# SCT12A0_BOOST.net
KiCad netlist of a schematic drawn in Altium Designer
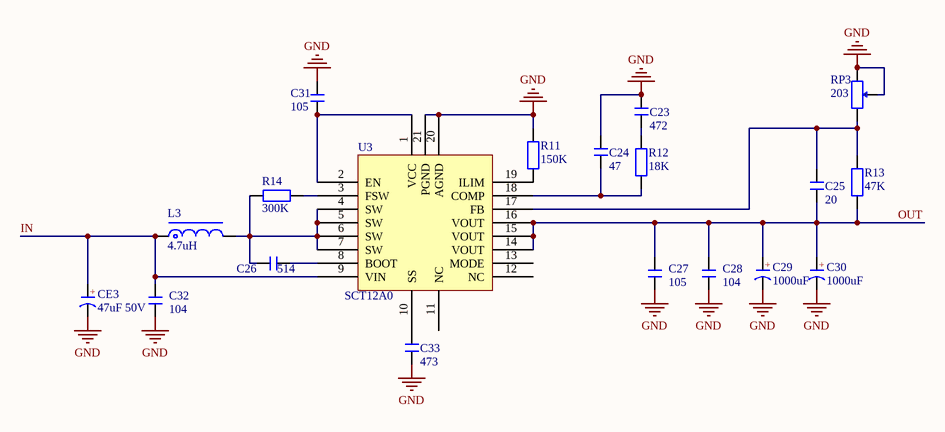
[diagram p0: SCT12A0 BOOST.SchDoc]

(export (version "E")
  (design (tool "Eeschema 10.0.6"))
  (components
    (comp (ref "C23")
      (value "472")
      (footprint "C 0805_L")
      (description "贴片电容")
      (libsource (lib "01 - 电容-电阻-电感") (part "C"))
    )
    (comp (ref "C24")
      (value "47")
      (footprint "C 0805_L")
      (description "贴片电容")
      (libsource (lib "01 - 电容-电阻-电感") (part "C"))
    )
    (comp (ref "C25")
      (value "20")
      (footprint "C 0805_L")
      (description "贴片电容")
      (libsource (lib "01 - 电容-电阻-电感") (part "C"))
    )
    (comp (ref "C26")
      (value "514")
      (footprint "C 0805_L")
      (description "贴片电容")
      (libsource (lib "01 - 电容-电阻-电感") (part "C"))
    )
    (comp (ref "C27")
      (value "105")
      (footprint "C 0805_L")
      (description "贴片电容")
      (libsource (lib "01 - 电容-电阻-电感") (part "C"))
    )
    (comp (ref "C28")
      (value "104")
      (footprint "C 0805_L")
      (description "贴片电容")
      (libsource (lib "01 - 电容-电阻-电感") (part "C"))
    )
    (comp (ref "C29")
      (value "1000uF")
      (footprint "CAP 7.5*16*25")
      (description "直插电解电容")
      (libsource (lib "01 - 电容-电阻-电感") (part "CE"))
    )
    (comp (ref "C30")
      (value "1000uF")
      (footprint "CAP 5.0*12.5*20")
      (description "直插电解电容")
      (libsource (lib "01 - 电容-电阻-电感") (part "CE"))
    )
    (comp (ref "C31")
      (value "105")
      (footprint "C 0805_L")
      (description "贴片电容")
      (libsource (lib "01 - 电容-电阻-电感") (part "C"))
    )
    (comp (ref "C32")
      (value "104")
      (footprint "C 0805_L")
      (description "贴片电容")
      (libsource (lib "01 - 电容-电阻-电感") (part "C"))
    )
    (comp (ref "C33")
      (value "473")
      (footprint "C 0805_L")
      (description "贴片电容")
      (libsource (lib "01 - 电容-电阻-电感") (part "C"))
    )
    (comp (ref "CE3")
      (value "47uF 50V")
      (footprint "CM C(5*5.4)")
      (description "贴片电解电容")
      (libsource (lib "01 - 电容-电阻-电感") (part "CE_SMD"))
    )
    (comp (ref "L3")
      (value "4.7uH")
      (footprint "CDRH127")
      (description "功率屏蔽电感")
      (libsource (lib "01 - 电容-电阻-电感") (part "L-CDRH"))
    )
    (comp (ref "R11")
      (value "150K")
      (footprint "R 0805_L")
      (description "贴片电阻")
      (libsource (lib "01 - 电容-电阻-电感") (part "R"))
    )
    (comp (ref "R12")
      (value "18K")
      (footprint "R 0805_L")
      (description "贴片电阻")
      (libsource (lib "01 - 电容-电阻-电感") (part "R"))
    )
    (comp (ref "R13")
      (value "47K")
      (footprint "R 0805_L")
      (description "贴片电阻")
      (libsource (lib "01 - 电容-电阻-电感") (part "R"))
    )
    (comp (ref "R14")
      (value "300K")
      (footprint "R 0805_L")
      (description "贴片电阻")
      (libsource (lib "01 - 电容-电阻-电感") (part "R"))
    )
    (comp (ref "RP3")
      (value "203")
      (footprint "3296W")
      (description "单联电位器")
      (libsource (lib "01 - 电容-电阻-电感") (part "RP"))
    )
    (comp (ref "U3")
      (value "SCT12A0")
      (footprint "DFN-20L (3.5x4.5)")
      (libsource (lib "10 - DC-DC") (part "SCT12A0"))
    )
  )
  (nets
    (net (code "1") (name "/IN") (class "Default")
      (node (ref "C32") (pin "2") (pinfunction "2_2") (pintype "passive"))
      (node (ref "CE3") (pin "1") (pinfunction "A_1") (pintype "passive"))
      (node (ref "L3") (pin "1") (pinfunction "1_1") (pintype "passive"))
      (node (ref "U3") (pin "9") (pinfunction "VIN_9") (pintype "passive"))
    )
    (net (code "2") (name "/OUT") (class "Default")
      (node (ref "C25") (pin "2") (pinfunction "2_2") (pintype "passive"))
      (node (ref "C27") (pin "2") (pinfunction "2_2") (pintype "passive"))
      (node (ref "C28") (pin "2") (pinfunction "2_2") (pintype "passive"))
      (node (ref "C29") (pin "1") (pinfunction "A_1") (pintype "passive"))
      (node (ref "C30") (pin "1") (pinfunction "A_1") (pintype "passive"))
      (node (ref "R13") (pin "2") (pinfunction "2_2") (pintype "passive"))
      (node (ref "U3") (pin "14") (pinfunction "VOUT_14") (pintype "passive"))
      (node (ref "U3") (pin "15") (pinfunction "VOUT_15") (pintype "passive"))
      (node (ref "U3") (pin "16") (pinfunction "VOUT_16") (pintype "passive"))
    )
    (net (code "3") (name "GND") (class "Default")
      (node (ref "C23") (pin "1") (pinfunction "1_1") (pintype "passive"))
      (node (ref "C24") (pin "1") (pinfunction "1_1") (pintype "passive"))
      (node (ref "C27") (pin "1") (pinfunction "1_1") (pintype "passive"))
      (node (ref "C28") (pin "1") (pinfunction "1_1") (pintype "passive"))
      (node (ref "C29") (pin "2") (pinfunction "K_2") (pintype "passive"))
      (node (ref "C30") (pin "2") (pinfunction "K_2") (pintype "passive"))
      (node (ref "C31") (pin "1") (pinfunction "1_1") (pintype "passive"))
      (node (ref "C32") (pin "1") (pinfunction "1_1") (pintype "passive"))
      (node (ref "C33") (pin "1") (pinfunction "1_1") (pintype "passive"))
      (node (ref "CE3") (pin "2") (pinfunction "K_2") (pintype "passive"))
      (node (ref "R11") (pin "1") (pinfunction "1_1") (pintype "passive"))
      (node (ref "RP3") (pin "1") (pinfunction "1_1") (pintype "passive"))
      (node (ref "RP3") (pin "2") (pinfunction "2_2") (pintype "passive"))
      (node (ref "U3") (pin "20") (pinfunction "AGND_20") (pintype "passive"))
      (node (ref "U3") (pin "21") (pinfunction "PGND_21") (pintype "passive"))
    )
    (net (code "4") (name "Net-(C23-Pad2)") (class "Default")
      (node (ref "C23") (pin "2") (pinfunction "2_2") (pintype "passive"))
      (node (ref "R12") (pin "1") (pinfunction "1_1") (pintype "passive"))
    )
    (net (code "5") (name "Net-(C26-Pad2)") (class "Default")
      (node (ref "C26") (pin "2") (pinfunction "2_2") (pintype "passive"))
      (node (ref "L3") (pin "2") (pinfunction "2_2") (pintype "passive"))
      (node (ref "R14") (pin "1") (pinfunction "1_1") (pintype "passive"))
      (node (ref "U3") (pin "4") (pinfunction "SW_4") (pintype "passive"))
      (node (ref "U3") (pin "5") (pinfunction "SW_5") (pintype "passive"))
      (node (ref "U3") (pin "6") (pinfunction "SW_6") (pintype "passive"))
      (node (ref "U3") (pin "7") (pinfunction "SW_7") (pintype "passive"))
    )
    (net (code "6") (name "Net-(U3-BOOT)") (class "Default")
      (node (ref "C26") (pin "1") (pinfunction "1_1") (pintype "passive"))
      (node (ref "U3") (pin "8") (pinfunction "BOOT_8") (pintype "passive"))
    )
    (net (code "7") (name "Net-(U3-COMP)") (class "Default")
      (node (ref "C24") (pin "2") (pinfunction "2_2") (pintype "passive"))
      (node (ref "R12") (pin "2") (pinfunction "2_2") (pintype "passive"))
      (node (ref "U3") (pin "18") (pinfunction "COMP_18") (pintype "passive"))
    )
    (net (code "8") (name "Net-(U3-EN)") (class "Default")
      (node (ref "C31") (pin "2") (pinfunction "2_2") (pintype "passive"))
      (node (ref "U3") (pin "1") (pinfunction "VCC_1") (pintype "passive"))
      (node (ref "U3") (pin "2") (pinfunction "EN_2") (pintype "passive"))
    )
    (net (code "9") (name "Net-(U3-FB)") (class "Default")
      (node (ref "C25") (pin "1") (pinfunction "1_1") (pintype "passive"))
      (node (ref "R13") (pin "1") (pinfunction "1_1") (pintype "passive"))
      (node (ref "RP3") (pin "3") (pinfunction "3_3") (pintype "passive"))
      (node (ref "U3") (pin "17") (pinfunction "FB_17") (pintype "passive"))
    )
    (net (code "10") (name "Net-(U3-FSW)") (class "Default")
      (node (ref "R14") (pin "2") (pinfunction "2_2") (pintype "passive"))
      (node (ref "U3") (pin "3") (pinfunction "FSW_3") (pintype "passive"))
    )
    (net (code "11") (name "Net-(U3-ILIM)") (class "Default")
      (node (ref "R11") (pin "2") (pinfunction "2_2") (pintype "passive"))
      (node (ref "U3") (pin "19") (pinfunction "ILIM_19") (pintype "passive"))
    )
    (net (code "12") (name "Net-(U3-SS)") (class "Default")
      (node (ref "C33") (pin "2") (pinfunction "2_2") (pintype "passive"))
      (node (ref "U3") (pin "10") (pinfunction "SS_10") (pintype "passive"))
    )
    (net (code "13") (name "unconnected-(U3-MODE-Pad13)") (class "Default")
      (node (ref "U3") (pin "13") (pinfunction "MODE_13") (pintype "passive"))
    )
    (net (code "14") (name "unconnected-(U3-NC-Pad11)") (class "Default")
      (node (ref "U3") (pin "11") (pinfunction "NC_11") (pintype "passive"))
    )
    (net (code "15") (name "unconnected-(U3-NC-Pad12)") (class "Default")
      (node (ref "U3") (pin "12") (pinfunction "NC_12") (pintype "passive"))
    )
  )
)
